# 1_P1.net
KiCad netlist of a schematic drawn in Altium Designer
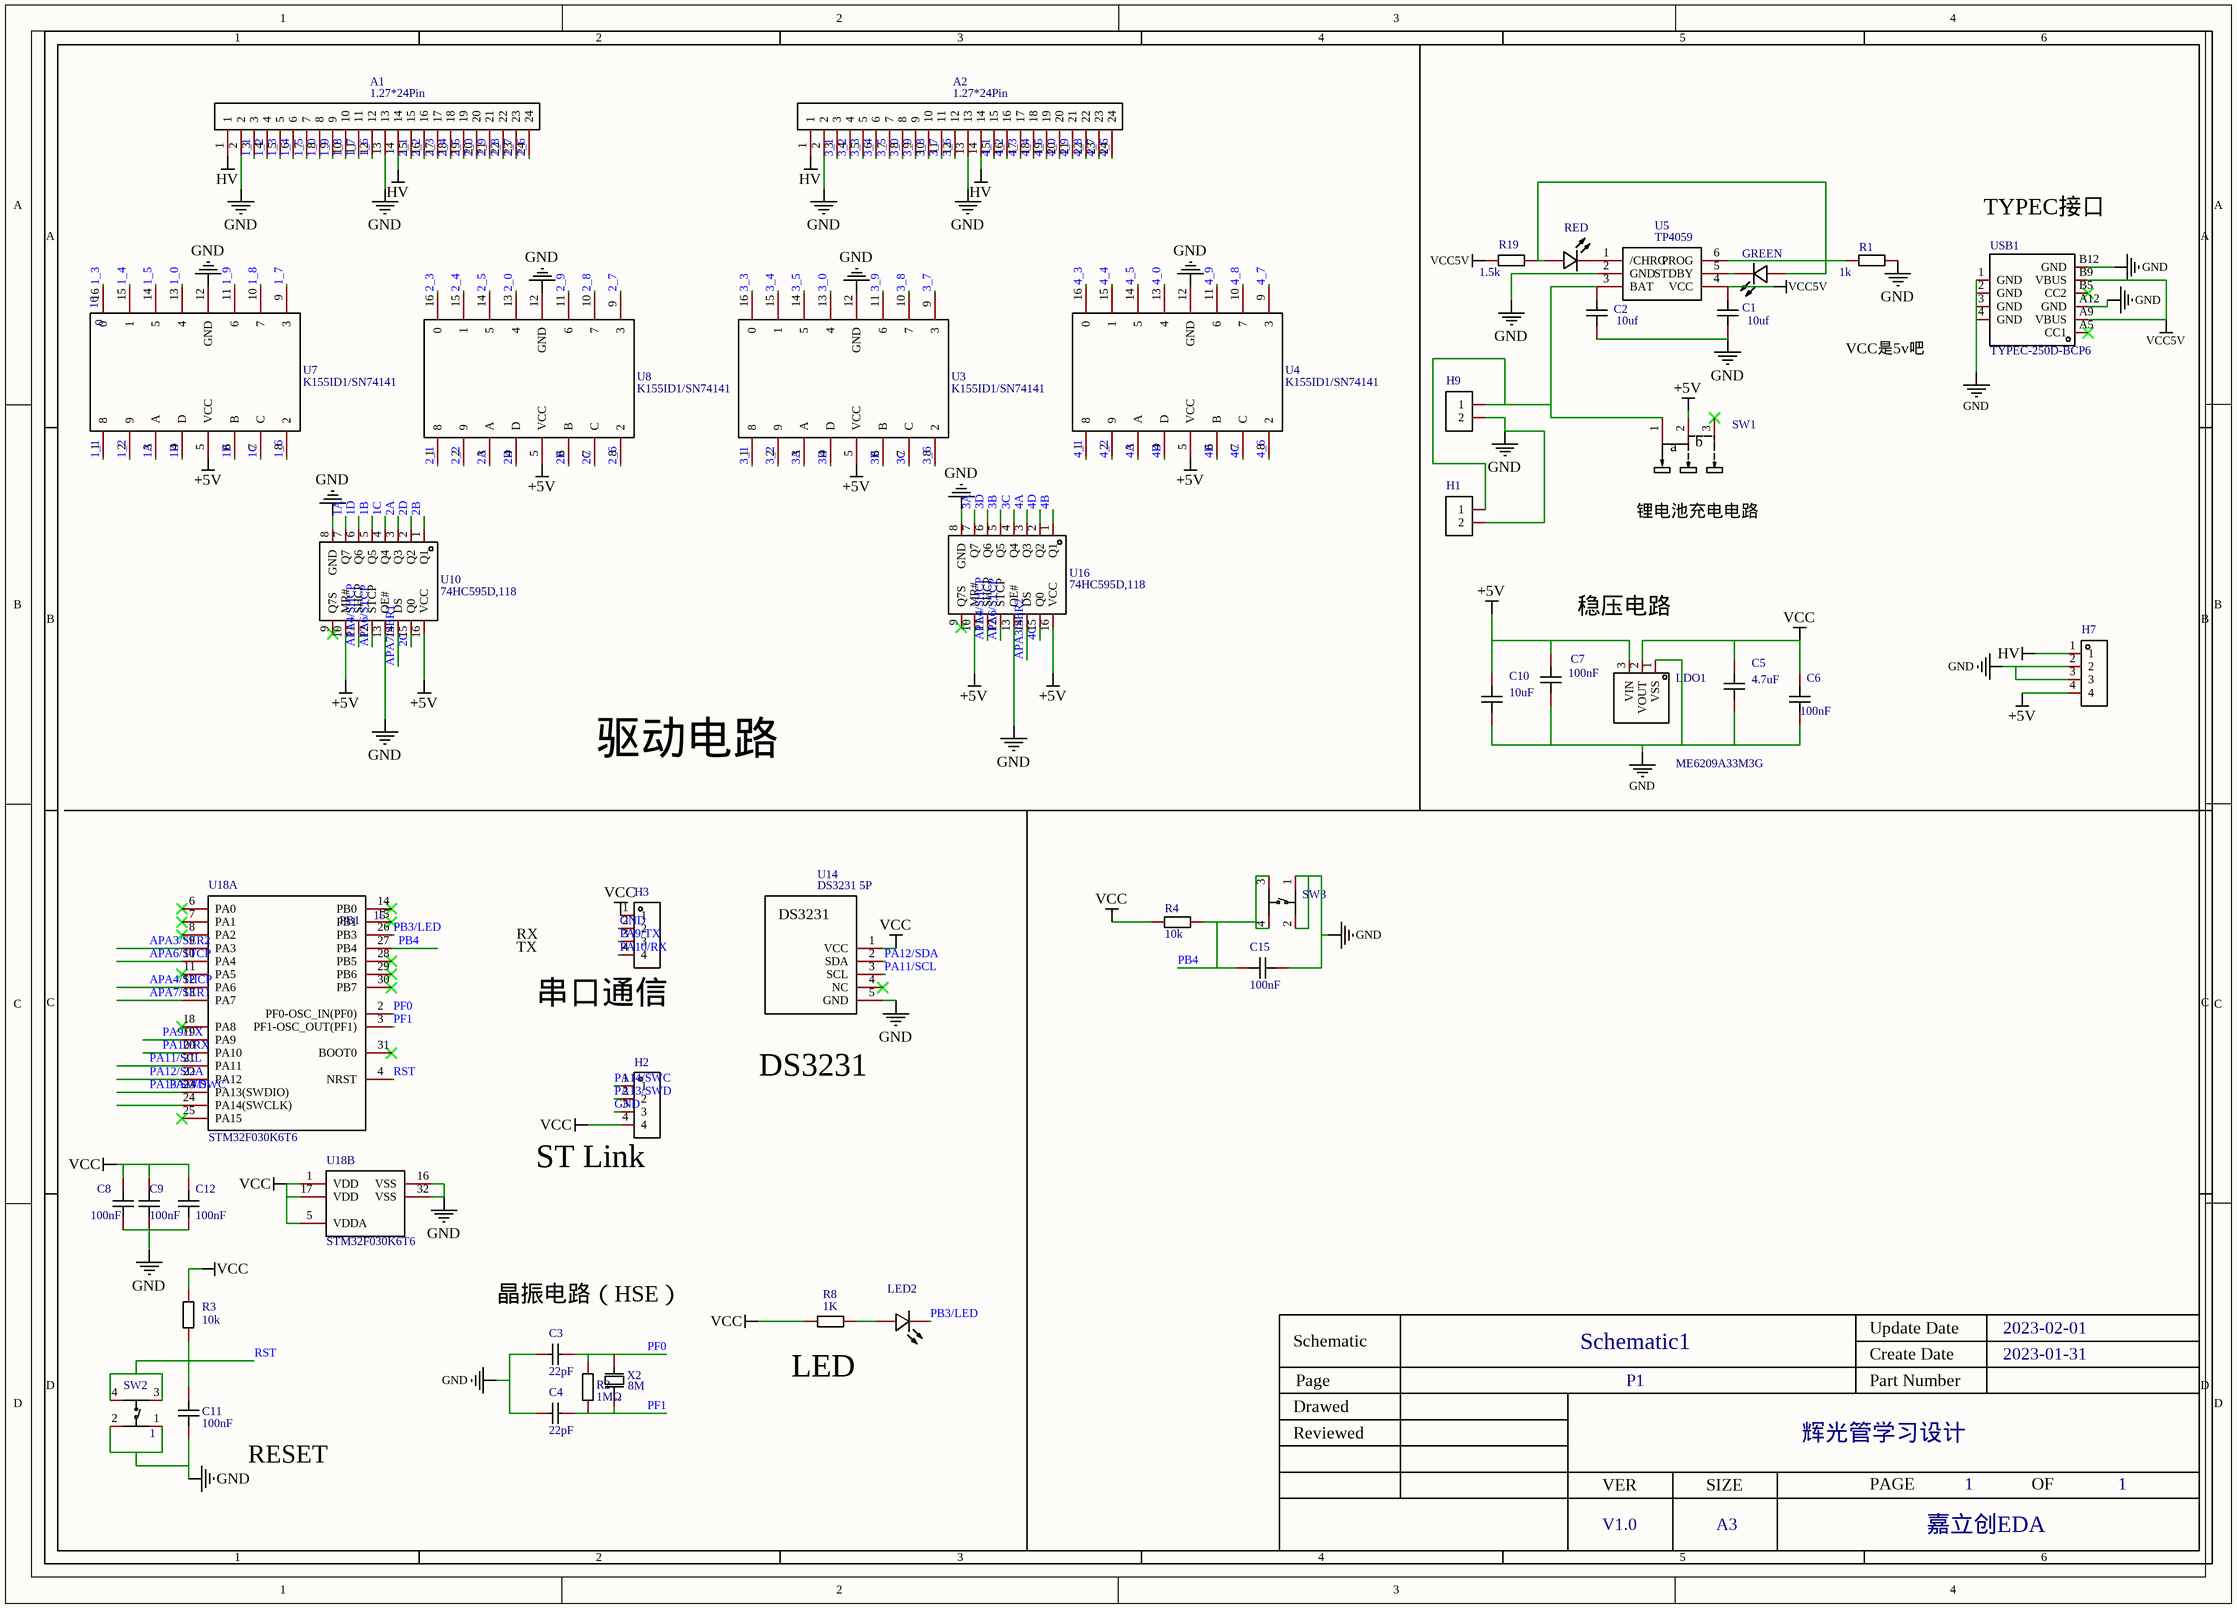
[diagram p0: 1_P1.schdoc]

(export (version "E")
  (design (tool "Eeschema 10.0.6"))
  (components
    (comp (ref "A1")
      (value "1.27*24Pin")
      (fields (field (name "NAME") "1.27*24Pin"))
      (libsource (lib "altium-import") (part "root_1_1.27*24Pin_"))
    )
    (comp (ref "A2")
      (value "1.27*24Pin")
      (fields (field (name "NAME") "1.27*24Pin"))
      (libsource (lib "altium-import") (part "root_1_1.27*24Pin_"))
    )
    (comp (ref "C1")
      (value "10uf")
      (description "容值:10uF;精度:±10%;额定电压:10V;温度系数:X7R;")
      (fields (field (name "MANUFACTURER") "FH(风华)") (field (name "MANUFACTURER PART") "0805B106K100NT"))
      (libsource (lib "altium-import") (part "root_3_0805B106K100NT_"))
    )
    (comp (ref "C2")
      (value "10uf")
      (description "容值:10uF;精度:±10%;额定电压:10V;温度系数:X7R;")
      (fields (field (name "MANUFACTURER") "FH(风华)") (field (name "MANUFACTURER PART") "0805B106K100NT"))
      (libsource (lib "altium-import") (part "root_3_0805B106K100NT_"))
    )
    (comp (ref "C3")
      (value "22pF")
      (description "容值:22pF;精度:±5%;额定电压:50V;温度系数:NP0;")
      (fields
        (field (name "MANUFACTURER") "YAGEO(国巨)")
        (field (name "MANUFACTURER PART") "CC0805JRNPO9BN220")
      )
      (libsource (lib "altium-import") (part "root_0_CC0805JRNPO9BN220_"))
    )
    (comp (ref "C4")
      (value "22pF")
      (description "容值:22pF;精度:±5%;额定电压:50V;温度系数:NP0;")
      (fields
        (field (name "MANUFACTURER") "YAGEO(国巨)")
        (field (name "MANUFACTURER PART") "CC0805JRNPO9BN220")
      )
      (libsource (lib "altium-import") (part "root_0_CC0805JRNPO9BN220_"))
    )
    (comp (ref "C5")
      (value "4.7uF")
      (description "容值:4.7uF;精度:±10%;额定电压:25V;温度系数:X5R;")
      (fields
        (field (name "MANUFACTURER") "YAGEO(国巨)")
        (field (name "MANUFACTURER PART") "CC0805KKX5R8BB475")
      )
      (libsource (lib "altium-import") (part "root_0_CC0805KKX5R8BB475_"))
    )
    (comp (ref "C6")
      (value "100nF")
      (description "容值:100nF;精度:±10%;额定电压:25V;温度系数:X7R;")
      (fields
        (field (name "MANUFACTURER") "CCTC(三环)")
        (field (name "MANUFACTURER PART") "TCC0805X7R104K250DTS")
      )
      (libsource (lib "altium-import") (part "root_0_TCC0805X7R104K250DTS_"))
    )
    (comp (ref "C7")
      (value "100nF")
      (description "容值:100nF;精度:±10%;额定电压:25V;温度系数:X7R;")
      (fields
        (field (name "MANUFACTURER") "CCTC(三环)")
        (field (name "MANUFACTURER PART") "TCC0805X7R104K250DTS")
      )
      (libsource (lib "altium-import") (part "root_0_TCC0805X7R104K250DTS_"))
    )
    (comp (ref "C8")
      (value "100nF")
      (description "容值:100nF;精度:±10%;额定电压:25V;温度系数:X6S;")
      (fields
        (field (name "MANUFACTURER") "muRata(村田)")
        (field (name "MANUFACTURER PART") "GRM033C81E104KE14D")
      )
      (libsource (lib "altium-import") (part "root_3_GRM033C81E104KE14D_"))
    )
    (comp (ref "C9")
      (value "100nF")
      (description "容值:100nF;精度:±10%;额定电压:25V;温度系数:X6S;")
      (fields
        (field (name "MANUFACTURER") "muRata(村田)")
        (field (name "MANUFACTURER PART") "GRM033C81E104KE14D")
      )
      (libsource (lib "altium-import") (part "root_3_GRM033C81E104KE14D_"))
    )
    (comp (ref "C10")
      (value "10uF")
      (description "容值:10uF;精度:±10%;额定电压:16V;温度系数:X7R;")
      (fields
        (field (name "MANUFACTURER") "SAMSUNG(三星)")
        (field (name "MANUFACTURER PART") "CL21B106KOQNNNE")
      )
      (libsource (lib "altium-import") (part "root_1_CL21B106KOQNNNE_"))
    )
    (comp (ref "C11")
      (value "100nF")
      (fields
        (field (name "NAME") "100nF")
        (field (name "MANUFACTURER") "火炬")
        (field (name "MANUFACTURER PART") "C0805B104M500NT")
      )
      (libsource (lib "altium-import") (part "root_1_100nF_"))
    )
    (comp (ref "C12")
      (value "100nF")
      (description "容值:100nF;精度:±10%;额定电压:25V;温度系数:X6S;")
      (fields
        (field (name "MANUFACTURER") "muRata(村田)")
        (field (name "MANUFACTURER PART") "GRM033C81E104KE14D")
      )
      (libsource (lib "altium-import") (part "root_3_GRM033C81E104KE14D_"))
    )
    (comp (ref "C15")
      (value "100nF")
      (description "容值:100nF;精度:±10%;额定电压:25V;温度系数:X6S;")
      (fields
        (field (name "MANUFACTURER") "muRata(村田)")
        (field (name "MANUFACTURER PART") "GRM033C81E104KE14D")
      )
      (libsource (lib "altium-import") (part "root_0_GRM033C81E104KE14D_"))
    )
    (comp (ref "GREEN")
      (value "NCD0805G1")
      (description "发光颜色:翠绿;")
      (fields (field (name "MANUFACTURER") "国星光电"))
      (libsource (lib "altium-import") (part "root_2_NCD0805G1_"))
    )
    (comp (ref "H1")
      (value "HDR-F_2.54_1x2P")
      (libsource (lib "altium-import") (part "root_0_mirrored_HDR-F_2.54_1x2P_"))
    )
    (comp (ref "H2")
      (value "HDR-F_2.54_1x4P")
      (libsource (lib "altium-import") (part "root_0_HDR-F_2.54_1x4P_"))
    )
    (comp (ref "H3")
      (value "HDR-F_2.54_1x4P")
      (libsource (lib "altium-import") (part "root_0_HDR-F_2.54_1x4P_"))
    )
    (comp (ref "H7")
      (value "HDR-F_2.54_1x4P")
      (libsource (lib "altium-import") (part "root_0_HDR-F_2.54_1x4P_"))
    )
    (comp (ref "H9")
      (value "HDR-F_2.54_1x2P")
      (libsource (lib "altium-import") (part "root_0_mirrored_HDR-F_2.54_1x2P_"))
    )
    (comp (ref "LDO1")
      (value "ME6209A33M3G")
      (description "输出类型:固定;输出极性:正;输出通道数:1;最大输入电压:18V;输出电压:3.3V;压差:80mV@(40mA);输出电流:250mA;电源纹波抑制比(PRSS):-;")
      (fields (field (name "NAME") "ME6209A33M3G") (field (name "MANUFACTURER") "MICRONE(南京微盟)"))
      (libsource (lib "altium-import") (part "root_3_ME6209A33M3G_"))
    )
    (comp (ref "LED2")
      (value "D21121300350-LED0805")
      (libsource (lib "altium-import") (part "root_2_D21121300350-LED0805_"))
    )
    (comp (ref "R1")
      (value "1k")
      (description "阻值:24k;精度:±1%;功率:125mW;温度系数:±100ppm/;最大工作电压:150V;工作温度范围:-55~+155;")
      (fields (field (name "MANUFACTURER") "YAGEO(国巨)") (field (name "MANUFACTURER PART") "RC0805FR-0724KL"))
      (libsource (lib "altium-import") (part "root_0_RC0805FR-0724KL_"))
    )
    (comp (ref "R2")
      (value "1MΩ")
      (fields
        (field (name "NAME") "1MΩ")
        (field (name "MANUFACTURER") "ResistorToday")
        (field (name "MANUFACTURER PART") "AECR0805F1M00K9")
      )
      (libsource (lib "altium-import") (part "root_1_1MΩ_"))
    )
    (comp (ref "R3")
      (value "10k")
      (description "阻值:24k;精度:±1%;功率:125mW;温度系数:±100ppm/;最大工作电压:150V;工作温度范围:-55~+155;")
      (fields (field (name "MANUFACTURER") "YAGEO(国巨)") (field (name "MANUFACTURER PART") "RC0805FR-0724KL"))
      (libsource (lib "altium-import") (part "root_1_RC0805FR-0724KL_"))
    )
    (comp (ref "R4")
      (value "10k")
      (description "电阻类型:薄膜电阻;阻值:10k;精度:±0.5%;功率:125mW;温度系数:±25ppm/;最大工作电压:100V;工作温度范围:-55~+155;")
      (fields (field (name "MANUFACTURER") "光颉(Viking)") (field (name "MANUFACTURER PART") "AR05DTCW1002"))
      (libsource (lib "altium-import") (part "root_0_AR05DTCW1002_"))
    )
    (comp (ref "R8")
      (value "1K")
      (fields
        (field (name "NAME") "1K")
        (field (name "MANUFACTURER") "ResistorToday")
        (field (name "MANUFACTURER PART") "AECR0805F150KK9")
      )
      (libsource (lib "altium-import") (part "root_2_1K_"))
    )
    (comp (ref "R19")
      (value "1.5k")
      (description "阻值:24k;精度:±1%;功率:125mW;温度系数:±100ppm/;最大工作电压:150V;工作温度范围:-55~+155;")
      (fields (field (name "MANUFACTURER") "YAGEO(国巨)") (field (name "MANUFACTURER PART") "RC0805FR-0724KL"))
      (libsource (lib "altium-import") (part "root_0_RC0805FR-0724KL_"))
    )
    (comp (ref "RED")
      (value "NCD0805G1")
      (description "发光颜色:翠绿;")
      (fields (field (name "MANUFACTURER") "国星光电"))
      (libsource (lib "altium-import") (part "root_0_NCD0805G1_"))
    )
    (comp (ref "SW1")
      (value "K3-1260D-K1")
      (fields (field (name "MANUFACTURER") "韩国韩荣"))
      (libsource (lib "altium-import") (part "root_0_K3-1260D-K1_"))
    )
    (comp (ref "SW2")
      (value "TC-6610F-5-260G")
      (fields (field (name "MANUFACTURER") "HCTL(华灿天禄)") (field (name "NUMBER") "1"))
      (libsource (lib "altium-import") (part "root_2_TC-6610F-5-260G_"))
    )
    (comp (ref "SW3")
      (value "TC-6610F-5-260G")
      (fields (field (name "MANUFACTURER") "HCTL(华灿天禄)"))
      (libsource (lib "altium-import") (part "root_3_TC-6610F-5-260G_"))
    )
    (comp (ref "U3")
      (value "K155ID1/SN74141")
      (fields (field (name "NAME") "K155ID1/SN74141"))
      (libsource (lib "altium-import") (part "root_1_K155ID1/SN74141_"))
    )
    (comp (ref "U4")
      (value "K155ID1/SN74141")
      (fields (field (name "NAME") "K155ID1/SN74141"))
      (libsource (lib "altium-import") (part "root_1_K155ID1/SN74141_"))
    )
    (comp (ref "U5")
      (value "TP4059")
      (fields (field (name "NAME") "TP4059") (field (name "MANUFACTURER") "TOPPOWER"))
      (libsource (lib "altium-import") (part "root_0_TP4059_"))
    )
    (comp (ref "U7")
      (value "K155ID1/SN74141")
      (fields
        (field (name "NAME") "K155ID1/SN74141")
        (field (name "NAME_1") "0")
        (field (name "NUMBER") "16")
      )
      (libsource (lib "altium-import") (part "root_1_K155ID1/SN74141_"))
    )
    (comp (ref "U8")
      (value "K155ID1/SN74141")
      (fields (field (name "NAME") "K155ID1/SN74141"))
      (libsource (lib "altium-import") (part "root_1_K155ID1/SN74141_"))
    )
    (comp (ref "U10")
      (value "74HC595D,118")
      (fields (field (name "NAME") "74HC595D,118") (field (name "MANUFACTURER") "Nexperia"))
      (libsource (lib "altium-import") (part "root_3_74HC595D,118_"))
    )
    (comp (ref "U14")
      (value "DS3231 5P")
      (fields (field (name "NAME") "DS3231 5P") (field (name "MANUFACTURER PART") "DS3231"))
      (libsource (lib "altium-import") (part "root_0_DS3231 5P_"))
    )
    (comp (ref "U16")
      (value "74HC595D,118")
      (fields (field (name "NAME") "74HC595D,118") (field (name "MANUFACTURER") "Nexperia"))
      (libsource (lib "altium-import") (part "root_3_74HC595D,118_"))
    )
    (comp (ref "U18")
      (value "STM32F030K6T6")
      (fields
        (field (name "NAME") "STM32F030K6T6")
        (field (name "MANUFACTURER") "ST(意法半导体)")
        (field (name "NAME_1") "PB1")
        (field (name "NUMBER") "15")
      )
      (libsource (lib "altium-import") (part "root_0_STM32F030K6T6_"))
    )
    (comp (ref "USB1")
      (value "TYPEC-250D-BCP6")
      (description "连接器类型:Type-C;标准:USB 3.1;公母:母座;触点数量:6;端口数量:1;安装方式:卧贴;额定电流 - 电源:3A;工作温度范围:-25~+85;焊接温度(最大值):260;")
      (fields (field (name "NAME") "TYPEC-250D-BCP6") (field (name "MANUFACTURER") "XUNPU(讯普)"))
      (libsource (lib "altium-import") (part "root_2_TYPEC-250D-BCP6_"))
    )
    (comp (ref "X2")
      (value "8M")
      (description "晶振类型:49S晶振;工作温度:-;")
      (fields
        (field (name "NAME") "8M")
        (field (name "MANUFACTURER") "JGHC(晶光华)")
        (field (name "MANUFACTURER PART") "49SAC08000182060")
      )
      (libsource (lib "altium-import") (part "root_1_49SAC08000182060_"))
    )
  )
  (nets
    (net (code "1") (name "+5V") (class "Default")
      (node (ref "C10") (pin "2") (pinfunction "2_2") (pintype "passive"))
      (node (ref "C7") (pin "2") (pinfunction "2_2") (pintype "passive"))
      (node (ref "H7") (pin "4") (pinfunction "4_4") (pintype "passive"))
      (node (ref "LDO1") (pin "3") (pinfunction "VIN_3") (pintype "passive"))
      (node (ref "SW1") (pin "2") (pinfunction "2_2") (pintype "passive"))
      (node (ref "U10") (pin "10") (pinfunction "MR#_10") (pintype "passive"))
      (node (ref "U10") (pin "16") (pinfunction "VCC_16") (pintype "passive"))
      (node (ref "U16") (pin "10") (pinfunction "MR#_10") (pintype "passive"))
      (node (ref "U16") (pin "16") (pinfunction "VCC_16") (pintype "passive"))
      (node (ref "U3") (pin "5") (pinfunction "VCC_5") (pintype "passive"))
      (node (ref "U4") (pin "5") (pinfunction "VCC_5") (pintype "passive"))
      (node (ref "U7") (pin "5") (pinfunction "VCC_5") (pintype "passive"))
      (node (ref "U8") (pin "5") (pinfunction "VCC_5") (pintype "passive"))
    )
    (net (code "2") (name "/1A") (class "Default")
      (node (ref "U10") (pin "7") (pinfunction "Q7_7") (pintype "passive"))
      (node (ref "U7") (pin "3") (pinfunction "A_3") (pintype "passive"))
    )
    (net (code "3") (name "/1B") (class "Default")
      (node (ref "U10") (pin "5") (pinfunction "Q5_5") (pintype "passive"))
      (node (ref "U7") (pin "6") (pinfunction "B_6") (pintype "passive"))
    )
    (net (code "4") (name "/1C") (class "Default")
      (node (ref "U10") (pin "4") (pinfunction "Q4_4") (pintype "passive"))
      (node (ref "U7") (pin "7") (pinfunction "C_7") (pintype "passive"))
    )
    (net (code "5") (name "/1D") (class "Default")
      (node (ref "U10") (pin "6") (pinfunction "Q6_6") (pintype "passive"))
      (node (ref "U7") (pin "4") (pinfunction "D_4") (pintype "passive"))
    )
    (net (code "6") (name "/1_0") (class "Default")
      (node (ref "A1") (pin "8") (pinfunction "8_8") (pintype "passive"))
      (node (ref "U7") (pin "13") (pinfunction "4_13") (pintype "passive"))
    )
    (net (code "7") (name "/1_1") (class "Default")
      (node (ref "A1") (pin "3") (pinfunction "3_3") (pintype "passive"))
      (node (ref "U7") (pin "1") (pinfunction "8_1") (pintype "passive"))
    )
    (net (code "8") (name "/1_2") (class "Default")
      (node (ref "A1") (pin "4") (pinfunction "4_4") (pintype "passive"))
      (node (ref "U7") (pin "2") (pinfunction "9_2") (pintype "passive"))
    )
    (net (code "9") (name "/1_3") (class "Default")
      (node (ref "A1") (pin "5") (pinfunction "5_5") (pintype "passive"))
      (node (ref "U7") (pin "16") (pinfunction "0_16") (pintype "passive"))
    )
    (net (code "10") (name "/1_4") (class "Default")
      (node (ref "A1") (pin "6") (pinfunction "6_6") (pintype "passive"))
      (node (ref "U7") (pin "15") (pinfunction "1_15") (pintype "passive"))
    )
    (net (code "11") (name "/1_5") (class "Default")
      (node (ref "A1") (pin "7") (pinfunction "7_7") (pintype "passive"))
      (node (ref "U7") (pin "14") (pinfunction "5_14") (pintype "passive"))
    )
    (net (code "12") (name "/1_6") (class "Default")
      (node (ref "A1") (pin "12") (pinfunction "12_12") (pintype "passive"))
      (node (ref "U7") (pin "8") (pinfunction "2_8") (pintype "passive"))
    )
    (net (code "13") (name "/1_7") (class "Default")
      (node (ref "A1") (pin "11") (pinfunction "11_11") (pintype "passive"))
      (node (ref "U7") (pin "9") (pinfunction "3_9") (pintype "passive"))
    )
    (net (code "14") (name "/1_8") (class "Default")
      (node (ref "A1") (pin "10") (pinfunction "10_10") (pintype "passive"))
      (node (ref "U7") (pin "10") (pinfunction "7_10") (pintype "passive"))
    )
    (net (code "15") (name "/1_9") (class "Default")
      (node (ref "A1") (pin "9") (pinfunction "9_9") (pintype "passive"))
      (node (ref "U7") (pin "11") (pinfunction "6_11") (pintype "passive"))
    )
    (net (code "16") (name "/2A") (class "Default")
      (node (ref "U10") (pin "3") (pinfunction "Q3_3") (pintype "passive"))
      (node (ref "U8") (pin "3") (pinfunction "A_3") (pintype "passive"))
    )
    (net (code "17") (name "/2B") (class "Default")
      (node (ref "U10") (pin "1") (pinfunction "Q1_1") (pintype "passive"))
      (node (ref "U8") (pin "6") (pinfunction "B_6") (pintype "passive"))
    )
    (net (code "18") (name "/2C") (class "Default")
      (node (ref "U10") (pin "15") (pinfunction "Q0_15") (pintype "passive"))
      (node (ref "U8") (pin "7") (pinfunction "C_7") (pintype "passive"))
    )
    (net (code "19") (name "/2D") (class "Default")
      (node (ref "U10") (pin "2") (pinfunction "Q2_2") (pintype "passive"))
      (node (ref "U8") (pin "4") (pinfunction "D_4") (pintype "passive"))
    )
    (net (code "20") (name "/2_0") (class "Default")
      (node (ref "A1") (pin "20") (pinfunction "20_20") (pintype "passive"))
      (node (ref "U8") (pin "13") (pinfunction "4_13") (pintype "passive"))
    )
    (net (code "21") (name "/2_1") (class "Default")
      (node (ref "A1") (pin "15") (pinfunction "15_15") (pintype "passive"))
      (node (ref "U8") (pin "1") (pinfunction "8_1") (pintype "passive"))
    )
    (net (code "22") (name "/2_2") (class "Default")
      (node (ref "A1") (pin "16") (pinfunction "16_16") (pintype "passive"))
      (node (ref "U8") (pin "2") (pinfunction "9_2") (pintype "passive"))
    )
    (net (code "23") (name "/2_3") (class "Default")
      (node (ref "A1") (pin "17") (pinfunction "17_17") (pintype "passive"))
      (node (ref "U8") (pin "16") (pinfunction "0_16") (pintype "passive"))
    )
    (net (code "24") (name "/2_4") (class "Default")
      (node (ref "A1") (pin "18") (pinfunction "18_18") (pintype "passive"))
      (node (ref "U8") (pin "15") (pinfunction "1_15") (pintype "passive"))
    )
    (net (code "25") (name "/2_5") (class "Default")
      (node (ref "A1") (pin "19") (pinfunction "19_19") (pintype "passive"))
      (node (ref "U8") (pin "14") (pinfunction "5_14") (pintype "passive"))
    )
    (net (code "26") (name "/2_6") (class "Default")
      (node (ref "A1") (pin "24") (pinfunction "24_24") (pintype "passive"))
      (node (ref "U8") (pin "8") (pinfunction "2_8") (pintype "passive"))
    )
    (net (code "27") (name "/2_7") (class "Default")
      (node (ref "A1") (pin "23") (pinfunction "23_23") (pintype "passive"))
      (node (ref "U8") (pin "9") (pinfunction "3_9") (pintype "passive"))
    )
    (net (code "28") (name "/2_8") (class "Default")
      (node (ref "A1") (pin "22") (pinfunction "22_22") (pintype "passive"))
      (node (ref "U8") (pin "10") (pinfunction "7_10") (pintype "passive"))
    )
    (net (code "29") (name "/2_9") (class "Default")
      (node (ref "A1") (pin "21") (pinfunction "21_21") (pintype "passive"))
      (node (ref "U8") (pin "11") (pinfunction "6_11") (pintype "passive"))
    )
    (net (code "30") (name "/3A") (class "Default")
      (node (ref "U16") (pin "7") (pinfunction "Q7_7") (pintype "passive"))
      (node (ref "U3") (pin "3") (pinfunction "A_3") (pintype "passive"))
    )
    (net (code "31") (name "/3B") (class "Default")
      (node (ref "U16") (pin "5") (pinfunction "Q5_5") (pintype "passive"))
      (node (ref "U3") (pin "6") (pinfunction "B_6") (pintype "passive"))
    )
    (net (code "32") (name "/3C") (class "Default")
      (node (ref "U16") (pin "4") (pinfunction "Q4_4") (pintype "passive"))
      (node (ref "U3") (pin "7") (pinfunction "C_7") (pintype "passive"))
    )
    (net (code "33") (name "/3D") (class "Default")
      (node (ref "U16") (pin "6") (pinfunction "Q6_6") (pintype "passive"))
      (node (ref "U3") (pin "4") (pinfunction "D_4") (pintype "passive"))
    )
    (net (code "34") (name "/3_0") (class "Default")
      (node (ref "A2") (pin "8") (pinfunction "8_8") (pintype "passive"))
      (node (ref "U3") (pin "13") (pinfunction "4_13") (pintype "passive"))
    )
    (net (code "35") (name "/3_1") (class "Default")
      (node (ref "A2") (pin "3") (pinfunction "3_3") (pintype "passive"))
      (node (ref "U3") (pin "1") (pinfunction "8_1") (pintype "passive"))
    )
    (net (code "36") (name "/3_2") (class "Default")
      (node (ref "A2") (pin "4") (pinfunction "4_4") (pintype "passive"))
      (node (ref "U3") (pin "2") (pinfunction "9_2") (pintype "passive"))
    )
    (net (code "37") (name "/3_3") (class "Default")
      (node (ref "A2") (pin "5") (pinfunction "5_5") (pintype "passive"))
      (node (ref "U3") (pin "16") (pinfunction "0_16") (pintype "passive"))
    )
    (net (code "38") (name "/3_4") (class "Default")
      (node (ref "A2") (pin "6") (pinfunction "6_6") (pintype "passive"))
      (node (ref "U3") (pin "15") (pinfunction "1_15") (pintype "passive"))
    )
    (net (code "39") (name "/3_5") (class "Default")
      (node (ref "A2") (pin "7") (pinfunction "7_7") (pintype "passive"))
      (node (ref "U3") (pin "14") (pinfunction "5_14") (pintype "passive"))
    )
    (net (code "40") (name "/3_6") (class "Default")
      (node (ref "A2") (pin "12") (pinfunction "12_12") (pintype "passive"))
      (node (ref "U3") (pin "8") (pinfunction "2_8") (pintype "passive"))
    )
    (net (code "41") (name "/3_7") (class "Default")
      (node (ref "A2") (pin "11") (pinfunction "11_11") (pintype "passive"))
      (node (ref "U3") (pin "9") (pinfunction "3_9") (pintype "passive"))
    )
    (net (code "42") (name "/3_8") (class "Default")
      (node (ref "A2") (pin "10") (pinfunction "10_10") (pintype "passive"))
      (node (ref "U3") (pin "10") (pinfunction "7_10") (pintype "passive"))
    )
    (net (code "43") (name "/3_9") (class "Default")
      (node (ref "A2") (pin "9") (pinfunction "9_9") (pintype "passive"))
      (node (ref "U3") (pin "11") (pinfunction "6_11") (pintype "passive"))
    )
    (net (code "44") (name "/4A") (class "Default")
      (node (ref "U16") (pin "3") (pinfunction "Q3_3") (pintype "passive"))
      (node (ref "U4") (pin "3") (pinfunction "A_3") (pintype "passive"))
    )
    (net (code "45") (name "/4B") (class "Default")
      (node (ref "U16") (pin "1") (pinfunction "Q1_1") (pintype "passive"))
      (node (ref "U4") (pin "6") (pinfunction "B_6") (pintype "passive"))
    )
    (net (code "46") (name "/4C") (class "Default")
      (node (ref "U16") (pin "15") (pinfunction "Q0_15") (pintype "passive"))
      (node (ref "U4") (pin "7") (pinfunction "C_7") (pintype "passive"))
    )
    (net (code "47") (name "/4D") (class "Default")
      (node (ref "U16") (pin "2") (pinfunction "Q2_2") (pintype "passive"))
      (node (ref "U4") (pin "4") (pinfunction "D_4") (pintype "passive"))
    )
    (net (code "48") (name "/4_0") (class "Default")
      (node (ref "A2") (pin "20") (pinfunction "20_20") (pintype "passive"))
      (node (ref "U4") (pin "13") (pinfunction "4_13") (pintype "passive"))
    )
    (net (code "49") (name "/4_1") (class "Default")
      (node (ref "A2") (pin "15") (pinfunction "15_15") (pintype "passive"))
      (node (ref "U4") (pin "1") (pinfunction "8_1") (pintype "passive"))
    )
    (net (code "50") (name "/4_2") (class "Default")
      (node (ref "A2") (pin "16") (pinfunction "16_16") (pintype "passive"))
      (node (ref "U4") (pin "2") (pinfunction "9_2") (pintype "passive"))
    )
    (net (code "51") (name "/4_3") (class "Default")
      (node (ref "A2") (pin "17") (pinfunction "17_17") (pintype "passive"))
      (node (ref "U4") (pin "16") (pinfunction "0_16") (pintype "passive"))
    )
    (net (code "52") (name "/4_4") (class "Default")
      (node (ref "A2") (pin "18") (pinfunction "18_18") (pintype "passive"))
      (node (ref "U4") (pin "15") (pinfunction "1_15") (pintype "passive"))
    )
    (net (code "53") (name "/4_5") (class "Default")
      (node (ref "A2") (pin "19") (pinfunction "19_19") (pintype "passive"))
      (node (ref "U4") (pin "14") (pinfunction "5_14") (pintype "passive"))
    )
    (net (code "54") (name "/4_6") (class "Default")
      (node (ref "A2") (pin "24") (pinfunction "24_24") (pintype "passive"))
      (node (ref "U4") (pin "8") (pinfunction "2_8") (pintype "passive"))
    )
    (net (code "55") (name "/4_7") (class "Default")
      (node (ref "A2") (pin "23") (pinfunction "23_23") (pintype "passive"))
      (node (ref "U4") (pin "9") (pinfunction "3_9") (pintype "passive"))
    )
    (net (code "56") (name "/4_8") (class "Default")
      (node (ref "A2") (pin "22") (pinfunction "22_22") (pintype "passive"))
      (node (ref "U4") (pin "10") (pinfunction "7_10") (pintype "passive"))
    )
    (net (code "57") (name "/4_9") (class "Default")
      (node (ref "A2") (pin "21") (pinfunction "21_21") (pintype "passive"))
      (node (ref "U4") (pin "11") (pinfunction "6_11") (pintype "passive"))
    )
    (net (code "58") (name "/APA3{slash}SER2") (class "Default")
      (node (ref "U16") (pin "14") (pinfunction "DS_14") (pintype "passive"))
      (node (ref "U18") (pin "9") (pinfunction "PA3_9") (pintype "passive"))
    )
    (net (code "59") (name "/APA4{slash}SHCP") (class "Default")
      (node (ref "U10") (pin "11") (pinfunction "SHCP_11") (pintype "passive"))
      (node (ref "U16") (pin "11") (pinfunction "SHCP_11") (pintype "passive"))
      (node (ref "U18") (pin "12") (pinfunction "PA6_12") (pintype "passive"))
    )
    (net (code "60") (name "/APA6{slash}STCP") (class "Default")
      (node (ref "U10") (pin "12") (pinfunction "STCP_12") (pintype "passive"))
      (node (ref "U16") (pin "12") (pinfunction "STCP_12") (pintype "passive"))
      (node (ref "U18") (pin "10") (pinfunction "PA4_10") (pintype "passive"))
    )
    (net (code "61") (name "/APA7{slash}SER1") (class "Default")
      (node (ref "U10") (pin "14") (pinfunction "DS_14") (pintype "passive"))
      (node (ref "U18") (pin "13") (pinfunction "PA7_13") (pintype "passive"))
    )
    (net (code "62") (name "/PA9{slash}TX") (class "Default")
      (node (ref "H3") (pin "3") (pinfunction "3_3") (pintype "passive"))
      (node (ref "U18") (pin "19") (pinfunction "PA9_19") (pintype "passive"))
    )
    (net (code "63") (name "/PA10{slash}RX") (class "Default")
      (node (ref "H3") (pin "4") (pinfunction "4_4") (pintype "passive"))
      (node (ref "U18") (pin "20") (pinfunction "PA10_20") (pintype "passive"))
    )
    (net (code "64") (name "/PA11{slash}SCL") (class "Default")
      (node (ref "U14") (pin "3") (pinfunction "SCL_3") (pintype "passive"))
      (node (ref "U18") (pin "21") (pinfunction "PA11_21") (pintype "passive"))
    )
    (net (code "65") (name "/PA12{slash}SDA") (class "Default")
      (node (ref "U14") (pin "2") (pinfunction "SDA_2") (pintype "passive"))
      (node (ref "U18") (pin "22") (pinfunction "PA12_22") (pintype "passive"))
    )
    (net (code "66") (name "/PA13{slash}SWD") (class "Default")
      (node (ref "H2") (pin "1") (pinfunction "1_1") (pintype "passive"))
      (node (ref "H2") (pin "2") (pinfunction "2_2") (pintype "passive"))
      (node (ref "U18") (pin "23") (pinfunction "PA13(SWDIO)_23") (pintype "passive"))
    )
    (net (code "67") (name "/PB3{slash}LED") (class "Default")
      (node (ref "LED2") (pin "2") (pinfunction "-_2") (pintype "passive"))
      (node (ref "U18") (pin "26") (pinfunction "PB3_26") (pintype "passive"))
    )
    (net (code "68") (name "/PB4") (class "Default")
      (node (ref "C15") (pin "1") (pinfunction "1_1") (pintype "passive"))
      (node (ref "R4") (pin "2") (pinfunction "2_2") (pintype "passive"))
      (node (ref "SW3") (pin "3") (pinfunction "C_3") (pintype "passive"))
      (node (ref "SW3") (pin "4") (pinfunction "D_4") (pintype "passive"))
      (node (ref "U18") (pin "27") (pinfunction "PB4_27") (pintype "passive"))
    )
    (net (code "69") (name "/PF0") (class "Default")
      (node (ref "C3") (pin "2") (pinfunction "2_2") (pintype "passive"))
      (node (ref "R2") (pin "2") (pinfunction "2_2") (pintype "passive"))
      (node (ref "U18") (pin "2") (pinfunction "PF0-OSC_IN(PF0)_2") (pintype "passive"))
      (node (ref "X2") (pin "2") (pinfunction "OSC2_2") (pintype "passive"))
    )
    (net (code "70") (name "/PF1") (class "Default")
      (node (ref "C4") (pin "2") (pinfunction "2_2") (pintype "passive"))
      (node (ref "R2") (pin "1") (pinfunction "1_1") (pintype "passive"))
      (node (ref "U18") (pin "3") (pinfunction "PF1-OSC_OUT(PF1)_3") (pintype "passive"))
      (node (ref "X2") (pin "1") (pinfunction "OSC1_1") (pintype "passive"))
    )
    (net (code "71") (name "/RST") (class "Default")
      (node (ref "C11") (pin "2") (pinfunction "2_2") (pintype "passive"))
      (node (ref "R3") (pin "1") (pinfunction "1_1") (pintype "passive"))
      (node (ref "SW2") (pin "3") (pinfunction "C_3") (pintype "passive"))
      (node (ref "SW2") (pin "4") (pinfunction "D_4") (pintype "passive"))
      (node (ref "U18") (pin "4") (pinfunction "NRST_4") (pintype "passive"))
    )
    (net (code "72") (name "GND") (class "Default")
      (node (ref "A1") (pin "13") (pinfunction "13_13") (pintype "passive"))
      (node (ref "A1") (pin "2") (pinfunction "2_2") (pintype "passive"))
      (node (ref "A2") (pin "13") (pinfunction "13_13") (pintype "passive"))
      (node (ref "A2") (pin "2") (pinfunction "2_2") (pintype "passive"))
      (node (ref "C1") (pin "2") (pinfunction "2_2") (pintype "passive"))
      (node (ref "C10") (pin "1") (pinfunction "1_1") (pintype "passive"))
      (node (ref "C11") (pin "1") (pinfunction "1_1") (pintype "passive"))
      (node (ref "C12") (pin "2") (pinfunction "2_2") (pintype "passive"))
      (node (ref "C15") (pin "2") (pinfunction "2_2") (pintype "passive"))
      (node (ref "C2") (pin "2") (pinfunction "2_2") (pintype "passive"))
      (node (ref "C3") (pin "1") (pinfunction "1_1") (pintype "passive"))
      (node (ref "C4") (pin "1") (pinfunction "1_1") (pintype "passive"))
      (node (ref "C5") (pin "1") (pinfunction "1_1") (pintype "passive"))
      (node (ref "C6") (pin "1") (pinfunction "1_1") (pintype "passive"))
      (node (ref "C7") (pin "1") (pinfunction "1_1") (pintype "passive"))
      (node (ref "C8") (pin "2") (pinfunction "2_2") (pintype "passive"))
      (node (ref "C9") (pin "2") (pinfunction "2_2") (pintype "passive"))
      (node (ref "H1") (pin "2") (pinfunction "2_2") (pintype "passive"))
      (node (ref "H2") (pin "3") (pinfunction "3_3") (pintype "passive"))
      (node (ref "H3") (pin "2") (pinfunction "2_2") (pintype "passive"))
      (node (ref "H7") (pin "2") (pinfunction "2_2") (pintype "passive"))
      (node (ref "H7") (pin "3") (pinfunction "3_3") (pintype "passive"))
      (node (ref "H9") (pin "2") (pinfunction "2_2") (pintype "passive"))
      (node (ref "LDO1") (pin "1") (pinfunction "VSS_1") (pintype "passive"))
      (node (ref "R1") (pin "2") (pinfunction "2_2") (pintype "passive"))
      (node (ref "SW2") (pin "1") (pinfunction "A_1") (pintype "passive"))
      (node (ref "SW2") (pin "2") (pinfunction "B_2") (pintype "passive"))
      (node (ref "SW3") (pin "1") (pinfunction "A_1") (pintype "passive"))
      (node (ref "SW3") (pin "2") (pinfunction "B_2") (pintype "passive"))
      (node (ref "U10") (pin "13") (pinfunction "OE#_13") (pintype "passive"))
      (node (ref "U10") (pin "8") (pinfunction "GND_8") (pintype "passive"))
      (node (ref "U14") (pin "5") (pinfunction "GND_5") (pintype "passive"))
      (node (ref "U16") (pin "13") (pinfunction "OE#_13") (pintype "passive"))
      (node (ref "U16") (pin "8") (pinfunction "GND_8") (pintype "passive"))
      (node (ref "U18") (pin "16") (pinfunction "VSS_16") (pintype "passive"))
      (node (ref "U18") (pin "32") (pinfunction "VSS_32") (pintype "passive"))
      (node (ref "U3") (pin "12") (pinfunction "GND_12") (pintype "passive"))
      (node (ref "U4") (pin "12") (pinfunction "GND_12") (pintype "passive"))
      (node (ref "U5") (pin "2") (pinfunction "GND_2") (pintype "passive"))
      (node (ref "U7") (pin "12") (pinfunction "GND_12") (pintype "passive"))
      (node (ref "U8") (pin "12") (pinfunction "GND_12") (pintype "passive"))
      (node (ref "USB1") (pin "1") (pinfunction "GND_1") (pintype "passive"))
      (node (ref "USB1") (pin "2") (pinfunction "GND_2") (pintype "passive"))
      (node (ref "USB1") (pin "3") (pinfunction "GND_3") (pintype "passive"))
      (node (ref "USB1") (pin "4") (pinfunction "GND_4") (pintype "passive"))
      (node (ref "USB1") (pin "A12") (pinfunction "GND_A12") (pintype "passive"))
      (node (ref "USB1") (pin "B12") (pinfunction "GND_B12") (pintype "passive"))
    )
    (net (code "73") (name "HV") (class "Default")
      (node (ref "A1") (pin "1") (pinfunction "1_1") (pintype "passive"))
      (node (ref "A1") (pin "14") (pinfunction "14_14") (pintype "passive"))
      (node (ref "A2") (pin "1") (pinfunction "1_1") (pintype "passive"))
      (node (ref "A2") (pin "14") (pinfunction "14_14") (pintype "passive"))
      (node (ref "H7") (pin "1") (pinfunction "1_1") (pintype "passive"))
    )
    (net (code "74") (name "Net-(GREEN-A)") (class "Default")
      (node (ref "GREEN") (pin "1") (pinfunction "A_1") (pintype "passive"))
      (node (ref "R19") (pin "2") (pinfunction "2_2") (pintype "passive"))
      (node (ref "RED") (pin "1") (pinfunction "A_1") (pintype "passive"))
    )
    (net (code "75") (name "Net-(GREEN-K)") (class "Default")
      (node (ref "GREEN") (pin "2") (pinfunction "K_2") (pintype "passive"))
      (node (ref "U5") (pin "5") (pinfunction "STDBY_5") (pintype "passive"))
    )
    (net (code "76") (name "Net-(LED2-+)") (class "Default")
      (node (ref "LED2") (pin "1") (pinfunction "+_1") (pintype "passive"))
      (node (ref "R8") (pin "1") (pinfunction "1_1") (pintype "passive"))
    )
    (net (code "77") (name "Net-(RED-K)") (class "Default")
      (node (ref "RED") (pin "2") (pinfunction "K_2") (pintype "passive"))
      (node (ref "U5") (pin "1") (pinfunction "/CHRG_1") (pintype "passive"))
    )
    (net (code "78") (name "Net-(U5-BAT)") (class "Default")
      (node (ref "C2") (pin "1") (pinfunction "1_1") (pintype "passive"))
      (node (ref "H1") (pin "1") (pinfunction "1_1") (pintype "passive"))
      (node (ref "H9") (pin "1") (pinfunction "1_1") (pintype "passive"))
      (node (ref "SW1") (pin "1") (pinfunction "1_1") (pintype "passive"))
      (node (ref "U5") (pin "3") (pinfunction "BAT_3") (pintype "passive"))
    )
    (net (code "79") (name "Net-(U5-PROG)") (class "Default")
      (node (ref "R1") (pin "1") (pinfunction "1_1") (pintype "passive"))
      (node (ref "U5") (pin "6") (pinfunction "PROG_6") (pintype "passive"))
    )
    (net (code "80") (name "VCC") (class "Default")
      (node (ref "C12") (pin "1") (pinfunction "1_1") (pintype "passive"))
      (node (ref "C5") (pin "2") (pinfunction "2_2") (pintype "passive"))
      (node (ref "C6") (pin "2") (pinfunction "2_2") (pintype "passive"))
      (node (ref "C8") (pin "1") (pinfunction "1_1") (pintype "passive"))
      (node (ref "C9") (pin "1") (pinfunction "1_1") (pintype "passive"))
      (node (ref "H2") (pin "4") (pinfunction "4_4") (pintype "passive"))
      (node (ref "H3") (pin "1") (pinfunction "1_1") (pintype "passive"))
      (node (ref "LDO1") (pin "2") (pinfunction "VOUT_2") (pintype "passive"))
      (node (ref "R3") (pin "2") (pinfunction "2_2") (pintype "passive"))
      (node (ref "R4") (pin "1") (pinfunction "1_1") (pintype "passive"))
      (node (ref "R8") (pin "2") (pinfunction "2_2") (pintype "passive"))
      (node (ref "U14") (pin "1") (pinfunction "VCC_1") (pintype "passive"))
      (node (ref "U18") (pin "1") (pinfunction "VDD_1") (pintype "passive"))
      (node (ref "U18") (pin "17") (pinfunction "VDD_17") (pintype "passive"))
      (node (ref "U18") (pin "5") (pinfunction "VDDA_5") (pintype "passive"))
    )
    (net (code "81") (name "VCC5V") (class "Default")
      (node (ref "C1") (pin "1") (pinfunction "1_1") (pintype "passive"))
      (node (ref "R19") (pin "1") (pinfunction "1_1") (pintype "passive"))
      (node (ref "U5") (pin "4") (pinfunction "VCC_4") (pintype "passive"))
      (node (ref "USB1") (pin "A9") (pinfunction "VBUS_A9") (pintype "passive"))
      (node (ref "USB1") (pin "B9") (pinfunction "VBUS_B9") (pintype "passive"))
    )
    (net (code "82") (name "unconnected-(SW1-Pad3)") (class "Default")
      (node (ref "SW1") (pin "3") (pinfunction "3_3") (pintype "passive+no_connect"))
    )
    (net (code "83") (name "unconnected-(U10-Q7S-Pad9)") (class "Default")
      (node (ref "U10") (pin "9") (pinfunction "Q7S_9") (pintype "passive+no_connect"))
    )
    (net (code "84") (name "unconnected-(U14-NC-Pad4)") (class "Default")
      (node (ref "U14") (pin "4") (pinfunction "NC_4") (pintype "passive+no_connect"))
    )
    (net (code "85") (name "unconnected-(U16-Q7S-Pad9)") (class "Default")
      (node (ref "U16") (pin "9") (pinfunction "Q7S_9") (pintype "passive+no_connect"))
    )
    (net (code "86") (name "unconnected-(U18A-BOOT0-Pad31)") (class "Default")
      (node (ref "U18") (pin "31") (pinfunction "BOOT0_31") (pintype "passive+no_connect"))
    )
    (net (code "87") (name "unconnected-(U18A-PA0-Pad6)") (class "Default")
      (node (ref "U18") (pin "6") (pinfunction "PA0_6") (pintype "passive+no_connect"))
    )
    (net (code "88") (name "unconnected-(U18A-PA1-Pad7)") (class "Default")
      (node (ref "U18") (pin "7") (pinfunction "PA1_7") (pintype "passive+no_connect"))
    )
    (net (code "89") (name "unconnected-(U18A-PA2-Pad8)") (class "Default")
      (node (ref "U18") (pin "8") (pinfunction "PA2_8") (pintype "passive+no_connect"))
    )
    (net (code "90") (name "unconnected-(U18A-PA5-Pad11)") (class "Default")
      (node (ref "U18") (pin "11") (pinfunction "PA5_11") (pintype "passive+no_connect"))
    )
    (net (code "91") (name "unconnected-(U18A-PA8-Pad18)") (class "Default")
      (node (ref "U18") (pin "18") (pinfunction "PA8_18") (pintype "passive+no_connect"))
    )
    (net (code "92") (name "unconnected-(U18A-PA14(SWCLK)-Pad24)") (class "Default")
      (node (ref "U18") (pin "24") (pinfunction "PA14(SWCLK)_24") (pintype "passive"))
    )
    (net (code "93") (name "unconnected-(U18A-PA15-Pad25)") (class "Default")
      (node (ref "U18") (pin "25") (pinfunction "PA15_25") (pintype "passive+no_connect"))
    )
    (net (code "94") (name "unconnected-(U18A-PB0-Pad14)") (class "Default")
      (node (ref "U18") (pin "14") (pinfunction "PB0_14") (pintype "passive+no_connect"))
    )
    (net (code "95") (name "unconnected-(U18A-PB1-Pad15)") (class "Default")
      (node (ref "U18") (pin "15") (pinfunction "PB1_15") (pintype "passive+no_connect"))
    )
    (net (code "96") (name "unconnected-(U18A-PB5-Pad28)") (class "Default")
      (node (ref "U18") (pin "28") (pinfunction "PB5_28") (pintype "passive+no_connect"))
    )
    (net (code "97") (name "unconnected-(U18A-PB6-Pad29)") (class "Default")
      (node (ref "U18") (pin "29") (pinfunction "PB6_29") (pintype "passive+no_connect"))
    )
    (net (code "98") (name "unconnected-(U18A-PB7-Pad30)") (class "Default")
      (node (ref "U18") (pin "30") (pinfunction "PB7_30") (pintype "passive+no_connect"))
    )
    (net (code "99") (name "unconnected-(USB1-CC1-PadA5)") (class "Default")
      (node (ref "USB1") (pin "A5") (pinfunction "CC1_A5") (pintype "passive+no_connect"))
    )
    (net (code "100") (name "unconnected-(USB1-CC2-PadB5)") (class "Default")
      (node (ref "USB1") (pin "B5") (pinfunction "CC2_B5") (pintype "passive+no_connect"))
    )
  )
)
